# Engine_Room_v3.net
KiCad netlist of a schematic drawn in EAGLE
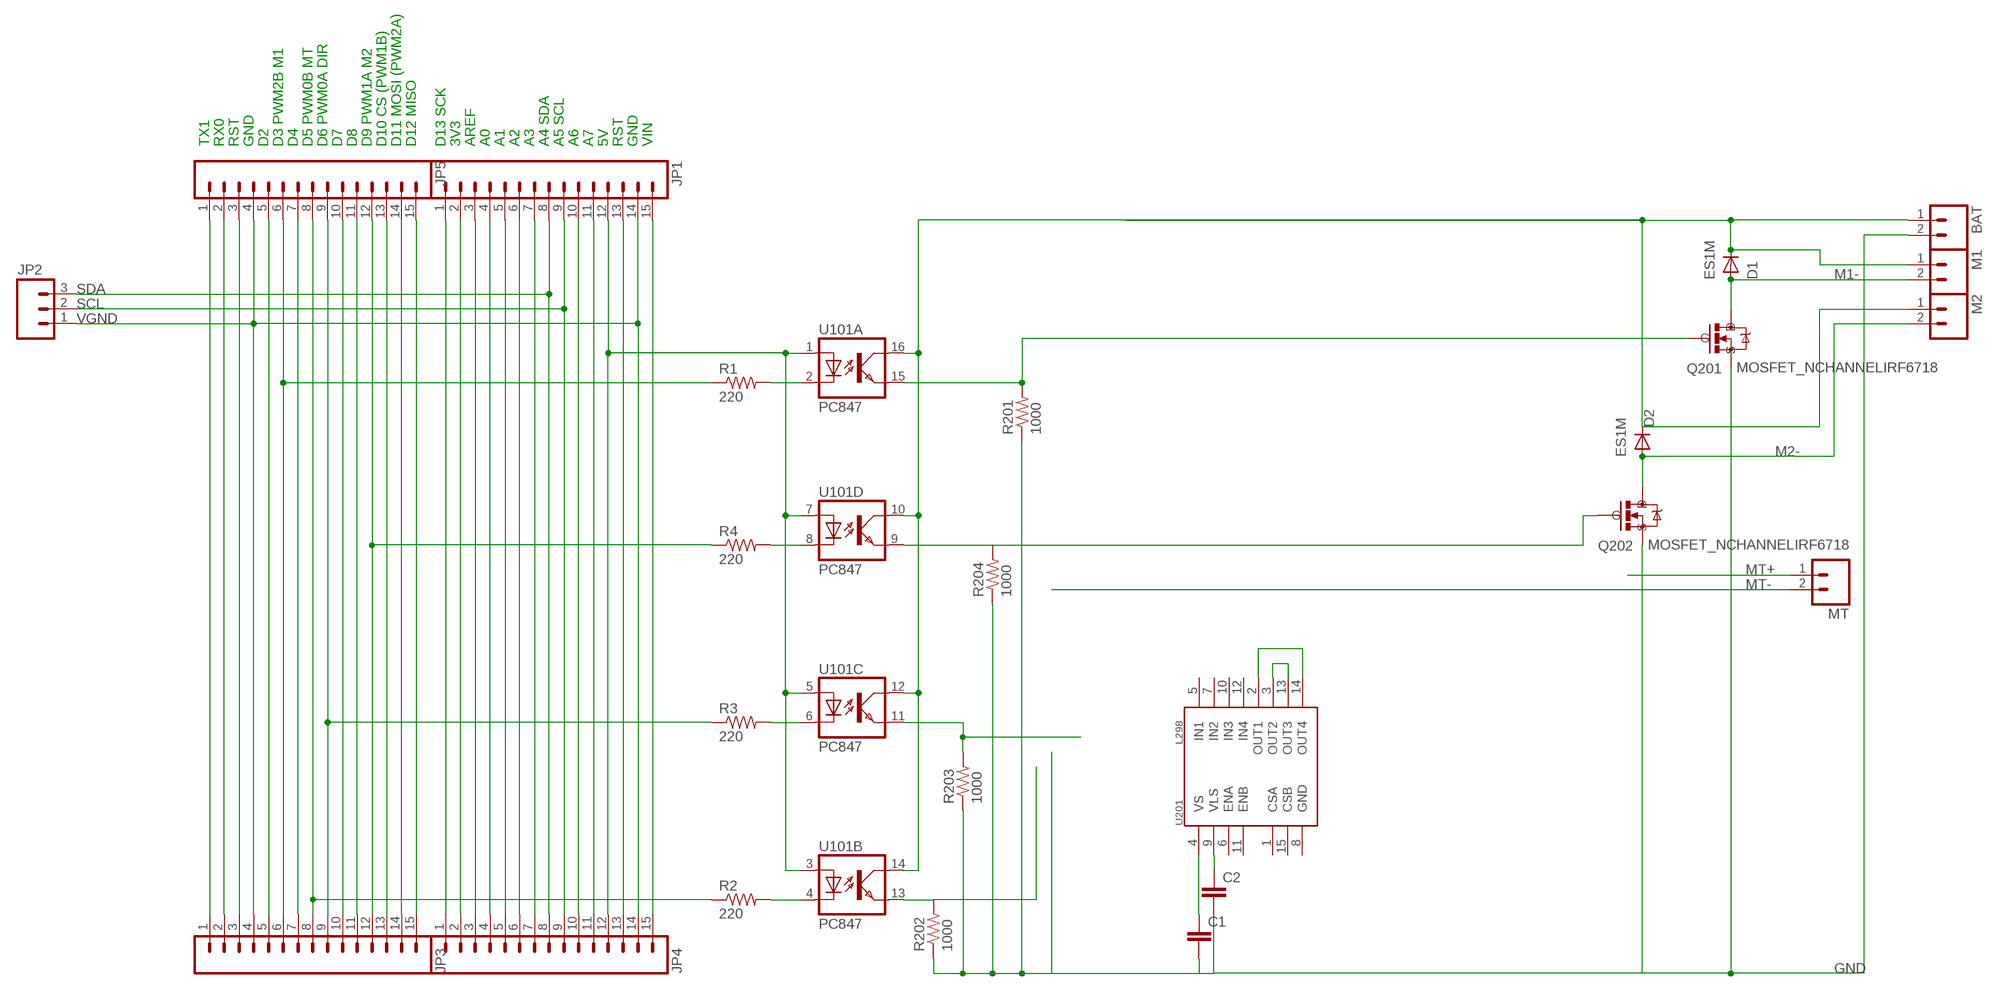
[diagram p0: schematic, sheet 1]

(export (version "E")
  (design (tool "Eeschema 10.0.6"))
  (components
    (comp (ref "BAT")
      (value "M02PTH4")
      (footprint "eagle-import:1X02_XTRA_BIG")
      (libsource (lib "eagle-import") (part "M02PTH4"))
    )
    (comp (ref "C1")
      (value "CAP0402-CAP")
      (footprint "eagle-import:0402-CAP")
      (libsource (lib "eagle-import") (part "CAP0402-CAP"))
    )
    (comp (ref "C2")
      (value "CAP0402-CAP")
      (footprint "eagle-import:0402-CAP")
      (libsource (lib "eagle-import") (part "CAP0402-CAP"))
    )
    (comp (ref "D1")
      (value "ES1M")
      (footprint "eagle-import:DO-214AC")
      (libsource (lib "eagle-import") (part "DIODE-DO-214AC"))
    )
    (comp (ref "D2")
      (value "ES1M")
      (footprint "eagle-import:DO-214AC")
      (libsource (lib "eagle-import") (part "DIODE-DO-214AC"))
    )
    (comp (ref "JP1")
      (value "M15LOCK")
      (footprint "eagle-import:1X15_LOCK")
      (libsource (lib "eagle-import") (part "M15LOCK"))
    )
    (comp (ref "JP2")
      (value "M03LOCK")
      (footprint "eagle-import:1X03_LOCK")
      (libsource (lib "eagle-import") (part "M03LOCK"))
    )
    (comp (ref "JP3")
      (value "M15")
      (footprint "eagle-import:1X15")
      (libsource (lib "eagle-import") (part "M15"))
    )
    (comp (ref "JP4")
      (value "M15")
      (footprint "eagle-import:1X15")
      (libsource (lib "eagle-import") (part "M15"))
    )
    (comp (ref "JP5")
      (value "M15LOCK")
      (footprint "eagle-import:1X15_LOCK")
      (libsource (lib "eagle-import") (part "M15LOCK"))
    )
    (comp (ref "M1")
      (value "M02PTH4")
      (footprint "eagle-import:1X02_XTRA_BIG")
      (libsource (lib "eagle-import") (part "M02PTH4"))
    )
    (comp (ref "M2")
      (value "M02PTH4")
      (footprint "eagle-import:1X02_XTRA_BIG")
      (libsource (lib "eagle-import") (part "M02PTH4"))
    )
    (comp (ref "MT")
      (value "M02PTH")
      (footprint "eagle-import:1X02")
      (libsource (lib "eagle-import") (part "M02PTH"))
    )
    (comp (ref "Q201")
      (value "MOSFET_NCHANNELIRF6718")
      (footprint "eagle-import:DIRECTFET_L6")
      (libsource (lib "eagle-import") (part "MOSFET_NCHANNELIRF6718"))
    )
    (comp (ref "Q202")
      (value "MOSFET_NCHANNELIRF6718")
      (footprint "eagle-import:DIRECTFET_L6")
      (libsource (lib "eagle-import") (part "MOSFET_NCHANNELIRF6718"))
    )
    (comp (ref "R1")
      (value "220")
      (footprint "eagle-import:0402-RES")
      (libsource (lib "eagle-import") (part "RESISTOR0402-RES"))
    )
    (comp (ref "R2")
      (value "220")
      (footprint "eagle-import:0402-RES")
      (libsource (lib "eagle-import") (part "RESISTOR0402-RES"))
    )
    (comp (ref "R3")
      (value "220")
      (footprint "eagle-import:0402-RES")
      (libsource (lib "eagle-import") (part "RESISTOR0402-RES"))
    )
    (comp (ref "R4")
      (value "220")
      (footprint "eagle-import:0402-RES")
      (libsource (lib "eagle-import") (part "RESISTOR0402-RES"))
    )
    (comp (ref "R201")
      (value "1000")
      (footprint "eagle-import:0402-RES")
      (libsource (lib "eagle-import") (part "RESISTOR0402-RES"))
    )
    (comp (ref "R202")
      (value "1000")
      (footprint "eagle-import:0402-RES")
      (libsource (lib "eagle-import") (part "RESISTOR0402-RES"))
    )
    (comp (ref "R203")
      (value "1000")
      (footprint "eagle-import:0402-RES")
      (libsource (lib "eagle-import") (part "RESISTOR0402-RES"))
    )
    (comp (ref "R204")
      (value "1000")
      (footprint "eagle-import:0402-RES")
      (libsource (lib "eagle-import") (part "RESISTOR0402-RES"))
    )
    (comp (ref "U101")
      (value "PC847")
      (footprint "eagle-import:DIL16")
      (libsource (lib "eagle-import") (part "PC847"))
    )
    (comp (ref "U201")
      (value "L298")
      (footprint "eagle-import:MULTIWATT15")
      (libsource (lib "eagle-import") (part "L298"))
    )
  )
  (nets
    (net (code "1") (name "/GND") (class "Default")
      (node (ref "BAT") (pin "2") (pinfunction "2_2") (pintype "passive"))
      (node (ref "C1") (pin "2") (pinfunction "2_2") (pintype "passive"))
      (node (ref "C2") (pin "2") (pinfunction "2_2") (pintype "passive"))
      (node (ref "Q201") (pin "S") (pinfunction "S_S") (pintype "passive"))
      (node (ref "Q202") (pin "S") (pinfunction "S_S") (pintype "passive"))
      (node (ref "R201") (pin "1") (pinfunction "1_1") (pintype "passive"))
      (node (ref "R202") (pin "1") (pinfunction "1_1") (pintype "passive"))
      (node (ref "R203") (pin "1") (pinfunction "1_1") (pintype "passive"))
      (node (ref "R204") (pin "1") (pinfunction "1_1") (pintype "passive"))
    )
    (net (code "2") (name "/M1-") (class "Default")
      (node (ref "D1") (pin "A") (pinfunction "A_A") (pintype "passive"))
      (node (ref "M1") (pin "2") (pinfunction "2_2") (pintype "passive"))
      (node (ref "Q201") (pin "D1") (pinfunction "D_D1") (pintype "passive"))
      (node (ref "Q201") (pin "D2") (pinfunction "D_D2") (pintype "passive"))
    )
    (net (code "3") (name "/M2-") (class "Default")
      (node (ref "D2") (pin "A") (pinfunction "A_A") (pintype "passive"))
      (node (ref "M2") (pin "2") (pinfunction "2_2") (pintype "passive"))
      (node (ref "Q202") (pin "D1") (pinfunction "D_D1") (pintype "passive"))
      (node (ref "Q202") (pin "D2") (pinfunction "D_D2") (pintype "passive"))
    )
    (net (code "4") (name "/MT+") (class "Default")
      (node (ref "MT") (pin "1") (pinfunction "1_1") (pintype "passive"))
    )
    (net (code "5") (name "/MT-") (class "Default")
      (node (ref "MT") (pin "2") (pinfunction "2_2") (pintype "passive"))
    )
    (net (code "6") (name "/SCL") (class "Default")
      (node (ref "JP1") (pin "9") (pinfunction "9_9") (pintype "passive"))
      (node (ref "JP2") (pin "2") (pinfunction "2_2") (pintype "passive"))
      (node (ref "JP4") (pin "9") (pinfunction "9_9") (pintype "passive"))
    )
    (net (code "7") (name "/SDA") (class "Default")
      (node (ref "JP1") (pin "8") (pinfunction "8_8") (pintype "passive"))
      (node (ref "JP2") (pin "3") (pinfunction "3_3") (pintype "passive"))
      (node (ref "JP4") (pin "8") (pinfunction "8_8") (pintype "passive"))
    )
    (net (code "8") (name "/VGND") (class "Default")
      (node (ref "JP1") (pin "14") (pinfunction "14_14") (pintype "passive"))
      (node (ref "JP2") (pin "1") (pinfunction "1_1") (pintype "passive"))
      (node (ref "JP3") (pin "4") (pinfunction "4_4") (pintype "passive"))
      (node (ref "JP4") (pin "14") (pinfunction "14_14") (pintype "passive"))
      (node (ref "JP5") (pin "4") (pinfunction "4_4") (pintype "passive"))
    )
    (net (code "9") (name "Net-(JP1-Pad1)") (class "Default")
      (node (ref "JP1") (pin "1") (pinfunction "1_1") (pintype "passive"))
      (node (ref "JP4") (pin "1") (pinfunction "1_1") (pintype "passive"))
    )
    (net (code "10") (name "Net-(JP1-Pad2)") (class "Default")
      (node (ref "JP1") (pin "2") (pinfunction "2_2") (pintype "passive"))
      (node (ref "JP4") (pin "2") (pinfunction "2_2") (pintype "passive"))
    )
    (net (code "11") (name "Net-(JP1-Pad3)") (class "Default")
      (node (ref "JP1") (pin "3") (pinfunction "3_3") (pintype "passive"))
      (node (ref "JP4") (pin "3") (pinfunction "3_3") (pintype "passive"))
    )
    (net (code "12") (name "Net-(JP1-Pad4)") (class "Default")
      (node (ref "JP1") (pin "4") (pinfunction "4_4") (pintype "passive"))
      (node (ref "JP4") (pin "4") (pinfunction "4_4") (pintype "passive"))
    )
    (net (code "13") (name "Net-(JP1-Pad5)") (class "Default")
      (node (ref "JP1") (pin "5") (pinfunction "5_5") (pintype "passive"))
      (node (ref "JP4") (pin "5") (pinfunction "5_5") (pintype "passive"))
    )
    (net (code "14") (name "Net-(JP1-Pad6)") (class "Default")
      (node (ref "JP1") (pin "6") (pinfunction "6_6") (pintype "passive"))
      (node (ref "JP4") (pin "6") (pinfunction "6_6") (pintype "passive"))
    )
    (net (code "15") (name "Net-(JP1-Pad7)") (class "Default")
      (node (ref "JP1") (pin "7") (pinfunction "7_7") (pintype "passive"))
      (node (ref "JP4") (pin "7") (pinfunction "7_7") (pintype "passive"))
    )
    (net (code "16") (name "Net-(JP1-Pad10)") (class "Default")
      (node (ref "JP1") (pin "10") (pinfunction "10_10") (pintype "passive"))
      (node (ref "JP4") (pin "10") (pinfunction "10_10") (pintype "passive"))
    )
    (net (code "17") (name "Net-(JP1-Pad11)") (class "Default")
      (node (ref "JP1") (pin "11") (pinfunction "11_11") (pintype "passive"))
      (node (ref "JP4") (pin "11") (pinfunction "11_11") (pintype "passive"))
    )
    (net (code "18") (name "Net-(JP1-Pad13)") (class "Default")
      (node (ref "JP1") (pin "13") (pinfunction "13_13") (pintype "passive"))
      (node (ref "JP4") (pin "13") (pinfunction "13_13") (pintype "passive"))
    )
    (net (code "19") (name "Net-(JP1-Pad15)") (class "Default")
      (node (ref "JP1") (pin "15") (pinfunction "15_15") (pintype "passive"))
      (node (ref "JP4") (pin "15") (pinfunction "15_15") (pintype "passive"))
    )
    (net (code "20") (name "Net-(JP3-Pad1)") (class "Default")
      (node (ref "JP3") (pin "1") (pinfunction "1_1") (pintype "passive"))
      (node (ref "JP5") (pin "1") (pinfunction "1_1") (pintype "passive"))
    )
    (net (code "21") (name "Net-(JP3-Pad2)") (class "Default")
      (node (ref "JP3") (pin "2") (pinfunction "2_2") (pintype "passive"))
      (node (ref "JP5") (pin "2") (pinfunction "2_2") (pintype "passive"))
    )
    (net (code "22") (name "Net-(JP3-Pad3)") (class "Default")
      (node (ref "JP3") (pin "3") (pinfunction "3_3") (pintype "passive"))
      (node (ref "JP5") (pin "3") (pinfunction "3_3") (pintype "passive"))
    )
    (net (code "23") (name "Net-(JP3-Pad5)") (class "Default")
      (node (ref "JP3") (pin "5") (pinfunction "5_5") (pintype "passive"))
      (node (ref "JP5") (pin "5") (pinfunction "5_5") (pintype "passive"))
    )
    (net (code "24") (name "Net-(JP3-Pad6)") (class "Default")
      (node (ref "JP3") (pin "6") (pinfunction "6_6") (pintype "passive"))
      (node (ref "JP5") (pin "6") (pinfunction "6_6") (pintype "passive"))
      (node (ref "R1") (pin "1") (pinfunction "1_1") (pintype "passive"))
    )
    (net (code "25") (name "Net-(JP3-Pad7)") (class "Default")
      (node (ref "JP3") (pin "7") (pinfunction "7_7") (pintype "passive"))
      (node (ref "JP5") (pin "7") (pinfunction "7_7") (pintype "passive"))
    )
    (net (code "26") (name "Net-(JP3-Pad8)") (class "Default")
      (node (ref "JP3") (pin "8") (pinfunction "8_8") (pintype "passive"))
      (node (ref "JP5") (pin "8") (pinfunction "8_8") (pintype "passive"))
      (node (ref "R2") (pin "1") (pinfunction "1_1") (pintype "passive"))
    )
    (net (code "27") (name "Net-(JP3-Pad9)") (class "Default")
      (node (ref "JP3") (pin "9") (pinfunction "9_9") (pintype "passive"))
      (node (ref "JP5") (pin "9") (pinfunction "9_9") (pintype "passive"))
      (node (ref "R3") (pin "1") (pinfunction "1_1") (pintype "passive"))
    )
    (net (code "28") (name "Net-(JP3-Pad10)") (class "Default")
      (node (ref "JP3") (pin "10") (pinfunction "10_10") (pintype "passive"))
      (node (ref "JP5") (pin "10") (pinfunction "10_10") (pintype "passive"))
    )
    (net (code "29") (name "Net-(JP3-Pad11)") (class "Default")
      (node (ref "JP3") (pin "11") (pinfunction "11_11") (pintype "passive"))
      (node (ref "JP5") (pin "11") (pinfunction "11_11") (pintype "passive"))
    )
    (net (code "30") (name "Net-(JP3-Pad12)") (class "Default")
      (node (ref "JP3") (pin "12") (pinfunction "12_12") (pintype "passive"))
      (node (ref "JP5") (pin "12") (pinfunction "12_12") (pintype "passive"))
      (node (ref "R4") (pin "1") (pinfunction "1_1") (pintype "passive"))
    )
    (net (code "31") (name "Net-(JP3-Pad13)") (class "Default")
      (node (ref "JP3") (pin "13") (pinfunction "13_13") (pintype "passive"))
      (node (ref "JP5") (pin "13") (pinfunction "13_13") (pintype "passive"))
    )
    (net (code "32") (name "Net-(JP3-Pad14)") (class "Default")
      (node (ref "JP3") (pin "14") (pinfunction "14_14") (pintype "passive"))
      (node (ref "JP5") (pin "14") (pinfunction "14_14") (pintype "passive"))
    )
    (net (code "33") (name "Net-(JP3-Pad15)") (class "Default")
      (node (ref "JP3") (pin "15") (pinfunction "15_15") (pintype "passive"))
      (node (ref "JP5") (pin "15") (pinfunction "15_15") (pintype "passive"))
    )
    (net (code "34") (name "Net-(U101A-A)") (class "Default")
      (node (ref "JP1") (pin "12") (pinfunction "12_12") (pintype "passive"))
      (node (ref "JP4") (pin "12") (pinfunction "12_12") (pintype "passive"))
      (node (ref "U101") (pin "1") (pinfunction "A_1") (pintype "passive"))
      (node (ref "U101") (pin "3") (pinfunction "A_3") (pintype "passive"))
      (node (ref "U101") (pin "5") (pinfunction "A_5") (pintype "passive"))
      (node (ref "U101") (pin "7") (pinfunction "A_7") (pintype "passive"))
    )
    (net (code "35") (name "Net-(U101A-C)") (class "Default")
      (node (ref "R1") (pin "2") (pinfunction "2_2") (pintype "passive"))
      (node (ref "U101") (pin "2") (pinfunction "C_2") (pintype "passive"))
    )
    (net (code "36") (name "Net-(U101A-COL)") (class "Default")
      (node (ref "BAT") (pin "1") (pinfunction "1_1") (pintype "passive"))
      (node (ref "D1") (pin "C") (pinfunction "C_C") (pintype "passive"))
      (node (ref "D2") (pin "C") (pinfunction "C_C") (pintype "passive"))
      (node (ref "M1") (pin "1") (pinfunction "1_1") (pintype "passive"))
      (node (ref "M2") (pin "1") (pinfunction "1_1") (pintype "passive"))
      (node (ref "U101") (pin "10") (pinfunction "COL_10") (pintype "passive"))
      (node (ref "U101") (pin "12") (pinfunction "COL_12") (pintype "passive"))
      (node (ref "U101") (pin "14") (pinfunction "COL_14") (pintype "passive"))
      (node (ref "U101") (pin "16") (pinfunction "COL_16") (pintype "passive"))
    )
    (net (code "37") (name "Net-(U101A-EMIT)") (class "Default")
      (node (ref "Q201") (pin "G") (pinfunction "G_G") (pintype "passive"))
      (node (ref "R201") (pin "2") (pinfunction "2_2") (pintype "passive"))
      (node (ref "U101") (pin "15") (pinfunction "EMIT_15") (pintype "passive"))
    )
    (net (code "38") (name "Net-(U101B-C)") (class "Default")
      (node (ref "R2") (pin "2") (pinfunction "2_2") (pintype "passive"))
      (node (ref "U101") (pin "4") (pinfunction "C_4") (pintype "passive"))
    )
    (net (code "39") (name "Net-(U101B-EMIT)") (class "Default")
      (node (ref "R202") (pin "2") (pinfunction "2_2") (pintype "passive"))
      (node (ref "U101") (pin "13") (pinfunction "EMIT_13") (pintype "passive"))
    )
    (net (code "40") (name "Net-(U101C-C)") (class "Default")
      (node (ref "R3") (pin "2") (pinfunction "2_2") (pintype "passive"))
      (node (ref "U101") (pin "6") (pinfunction "C_6") (pintype "passive"))
    )
    (net (code "41") (name "Net-(U101C-EMIT)") (class "Default")
      (node (ref "R203") (pin "2") (pinfunction "2_2") (pintype "passive"))
      (node (ref "U101") (pin "11") (pinfunction "EMIT_11") (pintype "passive"))
    )
    (net (code "42") (name "Net-(U101D-C)") (class "Default")
      (node (ref "R4") (pin "2") (pinfunction "2_2") (pintype "passive"))
      (node (ref "U101") (pin "8") (pinfunction "C_8") (pintype "passive"))
    )
    (net (code "43") (name "Net-(U101D-EMIT)") (class "Default")
      (node (ref "Q202") (pin "G") (pinfunction "G_G") (pintype "passive"))
      (node (ref "R204") (pin "2") (pinfunction "2_2") (pintype "passive"))
      (node (ref "U101") (pin "9") (pinfunction "EMIT_9") (pintype "passive"))
    )
    (net (code "44") (name "Net-(U201-OUT1)") (class "Default")
      (node (ref "U201") (pin "14") (pinfunction "OUT4_14") (pintype "bidirectional"))
      (node (ref "U201") (pin "2") (pinfunction "OUT1_2") (pintype "bidirectional"))
    )
    (net (code "45") (name "Net-(U201-OUT2)") (class "Default")
      (node (ref "U201") (pin "13") (pinfunction "OUT3_13") (pintype "bidirectional"))
      (node (ref "U201") (pin "3") (pinfunction "OUT2_3") (pintype "bidirectional"))
    )
    (net (code "46") (name "Net-(U201-VLS)") (class "Default")
      (node (ref "C2") (pin "1") (pinfunction "1_1") (pintype "passive"))
      (node (ref "U201") (pin "9") (pinfunction "VLS_9") (pintype "bidirectional"))
    )
    (net (code "47") (name "Net-(U201-VS)") (class "Default")
      (node (ref "C1") (pin "1") (pinfunction "1_1") (pintype "passive"))
      (node (ref "U201") (pin "4") (pinfunction "VS_4") (pintype "bidirectional"))
    )
    (net (code "48") (name "unconnected-(U201-CSA-Pad1)") (class "Default")
      (node (ref "U201") (pin "1") (pinfunction "CSA_1") (pintype "bidirectional"))
    )
    (net (code "49") (name "unconnected-(U201-CSB-Pad15)") (class "Default")
      (node (ref "U201") (pin "15") (pinfunction "CSB_15") (pintype "bidirectional"))
    )
    (net (code "50") (name "unconnected-(U201-ENA-Pad6)") (class "Default")
      (node (ref "U201") (pin "6") (pinfunction "ENA_6") (pintype "bidirectional"))
    )
    (net (code "51") (name "unconnected-(U201-ENB-Pad11)") (class "Default")
      (node (ref "U201") (pin "11") (pinfunction "ENB_11") (pintype "bidirectional"))
    )
    (net (code "52") (name "unconnected-(U201-GND-Pad8)") (class "Default")
      (node (ref "U201") (pin "8") (pinfunction "GND_8") (pintype "bidirectional"))
    )
    (net (code "53") (name "unconnected-(U201-IN1-Pad5)") (class "Default")
      (node (ref "U201") (pin "5") (pinfunction "IN1_5") (pintype "bidirectional"))
    )
    (net (code "54") (name "unconnected-(U201-IN2-Pad7)") (class "Default")
      (node (ref "U201") (pin "7") (pinfunction "IN2_7") (pintype "bidirectional"))
    )
    (net (code "55") (name "unconnected-(U201-IN3-Pad10)") (class "Default")
      (node (ref "U201") (pin "10") (pinfunction "IN3_10") (pintype "bidirectional"))
    )
    (net (code "56") (name "unconnected-(U201-IN4-Pad12)") (class "Default")
      (node (ref "U201") (pin "12") (pinfunction "IN4_12") (pintype "bidirectional"))
    )
  )
)
